# AIO_tracker_V1_0.net
KiCad netlist of a schematic drawn in EAGLE
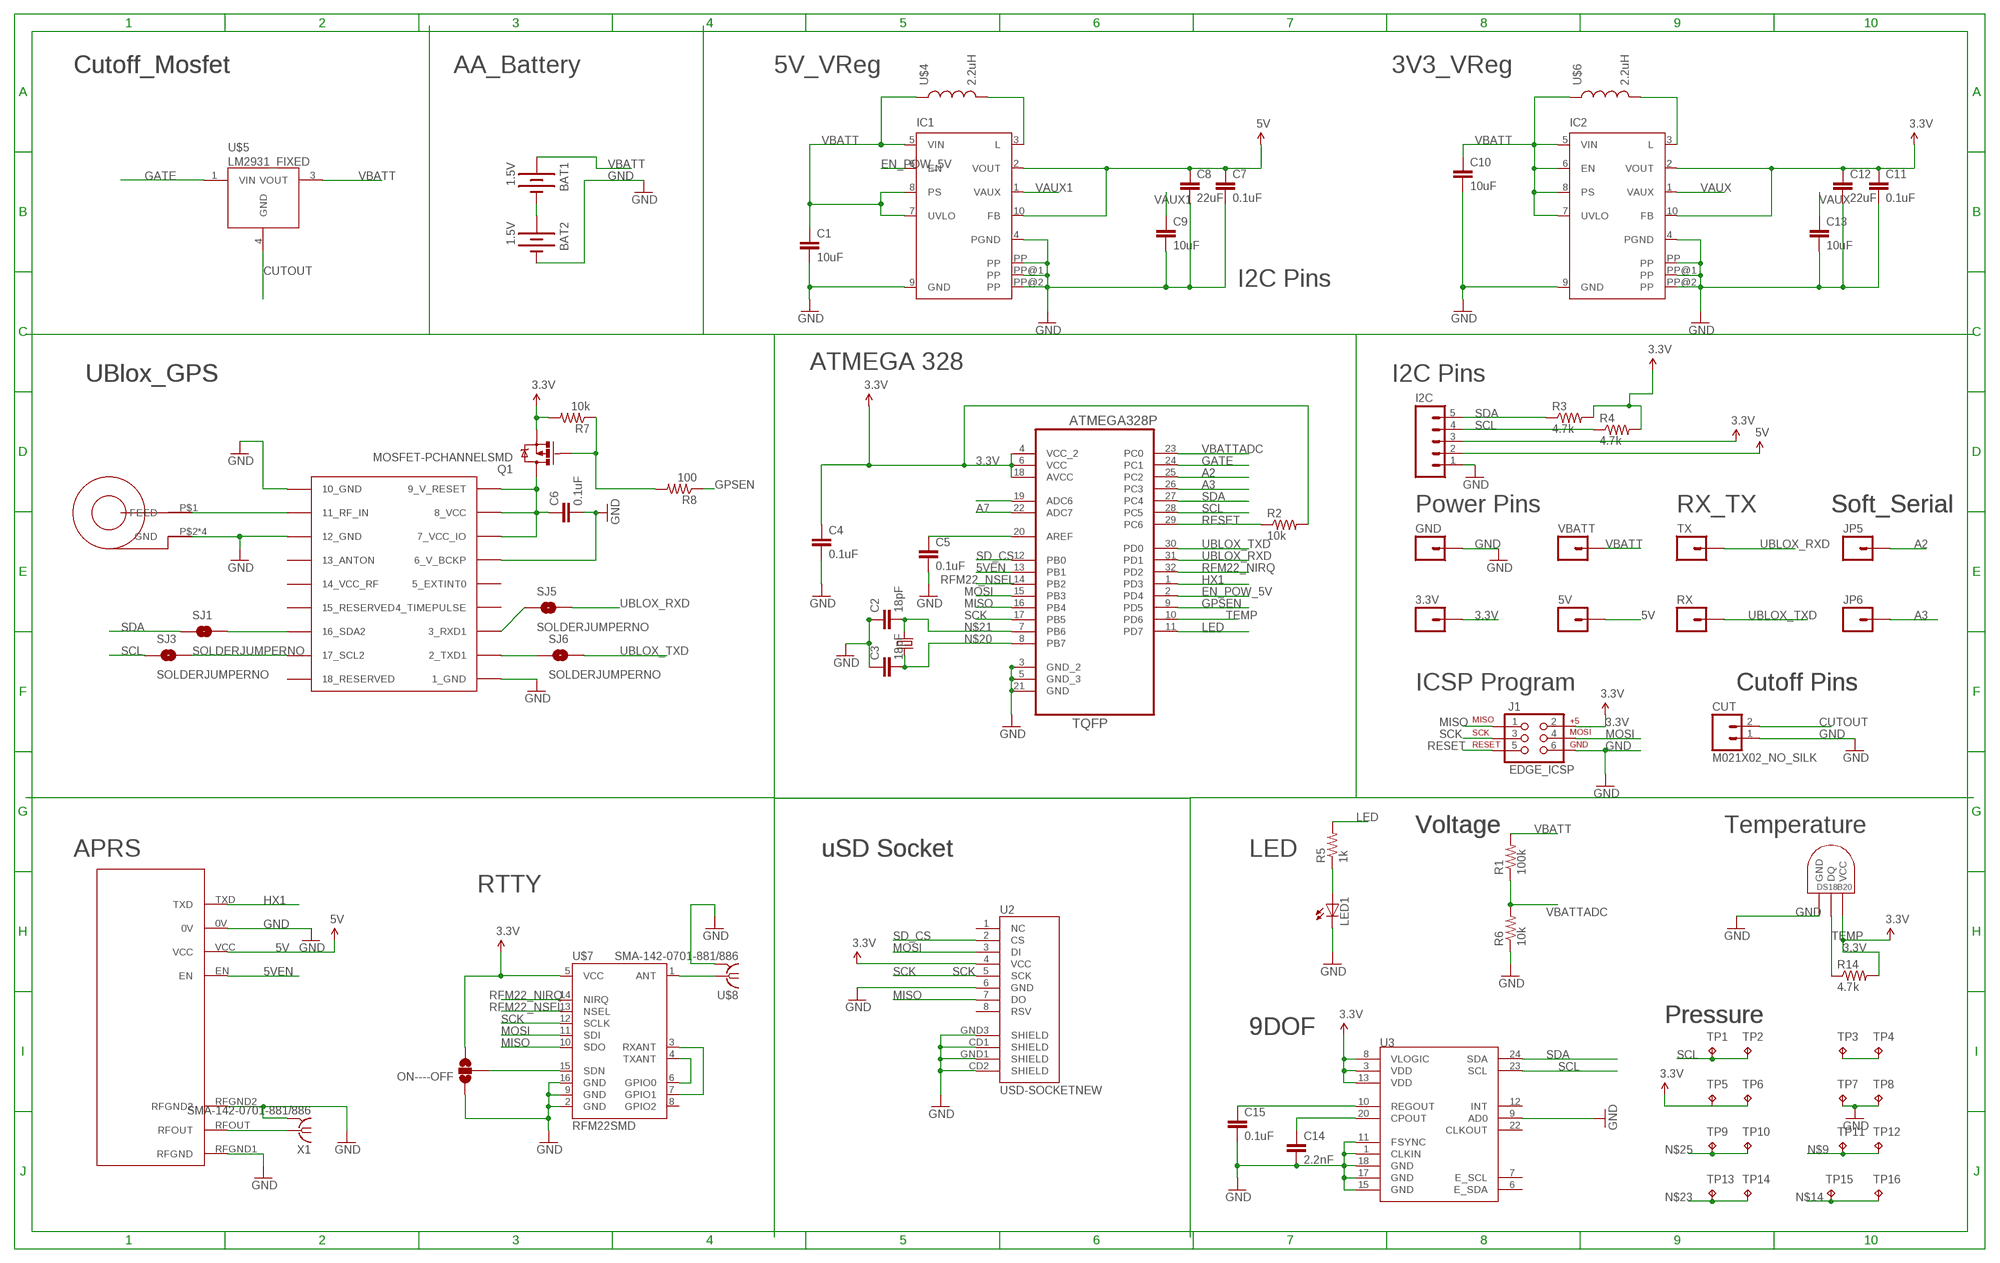
[diagram p0: schematic, sheet 1]

(export (version "E")
  (design (tool "Eeschema 10.0.6"))
  (components
    (comp (ref "3.3V")
      (value "M01SMDNS")
      (footprint "eagle-import:1X01NS")
      (libsource (lib "eagle-import") (part "M01SMDNS"))
    )
    (comp (ref "5V")
      (value "M01SMDNS")
      (footprint "eagle-import:1X01NS")
      (libsource (lib "eagle-import") (part "M01SMDNS"))
    )
    (comp (ref "BAT1")
      (value "1.5V")
      (footprint "eagle-import:BATTERY-AA-KIT")
      (libsource (lib "eagle-import") (part "BATTERYAA-KIT"))
    )
    (comp (ref "BAT2")
      (value "1.5V")
      (footprint "eagle-import:BATTERY-AA-KIT")
      (libsource (lib "eagle-import") (part "BATTERYAA-KIT"))
    )
    (comp (ref "C1")
      (value "10uF")
      (footprint "eagle-import:0805")
      (libsource (lib "eagle-import") (part "CAP0805"))
    )
    (comp (ref "C2")
      (value "18pF")
      (footprint "eagle-import:0603-CAP")
      (libsource (lib "eagle-import") (part "CAP0603-CAP"))
    )
    (comp (ref "C3")
      (value "18pF")
      (footprint "eagle-import:0603-CAP")
      (libsource (lib "eagle-import") (part "CAP0603-CAP"))
    )
    (comp (ref "C4")
      (value "0.1uF")
      (footprint "eagle-import:0603-CAP")
      (libsource (lib "eagle-import") (part "CAP0603-CAP"))
    )
    (comp (ref "C5")
      (value "0.1uF")
      (footprint "eagle-import:0603-CAP")
      (libsource (lib "eagle-import") (part "CAP0603-CAP"))
    )
    (comp (ref "C6")
      (value "0.1uF")
      (footprint "eagle-import:0603-CAP")
      (libsource (lib "eagle-import") (part "CAP0603-CAP"))
    )
    (comp (ref "C7")
      (value "0.1uF")
      (footprint "eagle-import:0603-CAP")
      (libsource (lib "eagle-import") (part "CAP0603-CAP"))
    )
    (comp (ref "C8")
      (value "22uF")
      (footprint "eagle-import:0805")
      (libsource (lib "eagle-import") (part "CAP0805"))
    )
    (comp (ref "C9")
      (value "10uF")
      (footprint "eagle-import:0805")
      (libsource (lib "eagle-import") (part "CAP0805"))
    )
    (comp (ref "C10")
      (value "10uF")
      (footprint "eagle-import:0805")
      (libsource (lib "eagle-import") (part "CAP0805"))
    )
    (comp (ref "C11")
      (value "0.1uF")
      (footprint "eagle-import:0603-CAP")
      (libsource (lib "eagle-import") (part "CAP0603-CAP"))
    )
    (comp (ref "C12")
      (value "22uF")
      (footprint "eagle-import:0805")
      (libsource (lib "eagle-import") (part "CAP0805"))
    )
    (comp (ref "C13")
      (value "10uF")
      (footprint "eagle-import:0805")
      (libsource (lib "eagle-import") (part "CAP0805"))
    )
    (comp (ref "C14")
      (value "2.2nF")
      (footprint "eagle-import:0603-CAP")
      (libsource (lib "eagle-import") (part "CAP0603-CAP"))
    )
    (comp (ref "C15")
      (value "0.1uF")
      (footprint "eagle-import:0603-CAP")
      (libsource (lib "eagle-import") (part "CAP0603-CAP"))
    )
    (comp (ref "CUT")
      (value "M021X02_NO_SILK")
      (footprint "eagle-import:1X02_NO_SILK")
      (libsource (lib "eagle-import") (part "M021X02_NO_SILK"))
    )
    (comp (ref "GND")
      (value "M01SMDNS")
      (footprint "eagle-import:1X01NS")
      (libsource (lib "eagle-import") (part "M01SMDNS"))
    )
    (comp (ref "I2C")
      (value "M05NO_SILK")
      (footprint "eagle-import:1X05_NO_SILK")
      (libsource (lib "eagle-import") (part "M05NO_SILK"))
    )
    (comp (ref "IC1")
      (value "TPS61201")
      (footprint "eagle-import:S-PDSO-N10")
      (fields (field (name "MPN") "TPS61201DRCT"))
      (libsource (lib "eagle-import") (part "TPS61201"))
    )
    (comp (ref "IC2")
      (value "TPS61201")
      (footprint "eagle-import:S-PDSO-N10")
      (fields (field (name "MPN") "TPS61201DRCT"))
      (libsource (lib "eagle-import") (part "TPS61201"))
    )
    (comp (ref "J1")
      (value "EDGE_ICSP")
      (footprint "eagle-import:EDGE_MOUNTED_ICSP")
      (libsource (lib "eagle-import") (part "EDGE_ICSP"))
    )
    (comp (ref "JP5")
      (value "M01PTH")
      (footprint "eagle-import:1X01")
      (libsource (lib "eagle-import") (part "M01PTH"))
    )
    (comp (ref "JP6")
      (value "M01PTH")
      (footprint "eagle-import:1X01")
      (libsource (lib "eagle-import") (part "M01PTH"))
    )
    (comp (ref "LED1")
      (value "LED0603")
      (footprint "eagle-import:LED-0603")
      (libsource (lib "eagle-import") (part "LED0603"))
    )
    (comp (ref "ON----OFF")
      (value "SOLDERJUMPER_2WAY-OLDT")
      (footprint "eagle-import:SJ_2")
      (libsource (lib "eagle-import") (part "SOLDERJUMPER_2WAY-OLDT"))
    )
    (comp (ref "Q1")
      (value "MOSFET-PCHANNELSMD")
      (footprint "eagle-import:SOT23-3")
      (libsource (lib "eagle-import") (part "MOSFET-PCHANNELSMD"))
    )
    (comp (ref "R1")
      (value "100k")
      (footprint "eagle-import:0603-RES")
      (libsource (lib "eagle-import") (part "RESISTOR0603-RES"))
    )
    (comp (ref "R2")
      (value "10k")
      (footprint "eagle-import:0603-RES")
      (libsource (lib "eagle-import") (part "RESISTOR0603-RES"))
    )
    (comp (ref "R3")
      (value "4.7k")
      (footprint "eagle-import:0603-RES")
      (libsource (lib "eagle-import") (part "RESISTOR0603-RES"))
    )
    (comp (ref "R4")
      (value "4.7k")
      (footprint "eagle-import:0603-RES")
      (libsource (lib "eagle-import") (part "RESISTOR0603-RES"))
    )
    (comp (ref "R5")
      (value "1k")
      (footprint "eagle-import:0603-RES")
      (libsource (lib "eagle-import") (part "RESISTOR0603-RES"))
    )
    (comp (ref "R6")
      (value "10k")
      (footprint "eagle-import:0603-RES")
      (libsource (lib "eagle-import") (part "RESISTOR0603-RES"))
    )
    (comp (ref "R7")
      (value "10k")
      (footprint "eagle-import:0603-RES")
      (libsource (lib "eagle-import") (part "RESISTOR0603-RES"))
    )
    (comp (ref "R8")
      (value "100")
      (footprint "eagle-import:0603-RES")
      (libsource (lib "eagle-import") (part "RESISTOR0603-RES"))
    )
    (comp (ref "R14")
      (value "4.7k")
      (footprint "eagle-import:0603-RES")
      (libsource (lib "eagle-import") (part "RESISTOR0603-RES"))
    )
    (comp (ref "RX")
      (value "M01PTH")
      (footprint "eagle-import:1X01")
      (libsource (lib "eagle-import") (part "M01PTH"))
    )
    (comp (ref "SJ1")
      (value "SOLDERJUMPERNO")
      (footprint "eagle-import:SJ_2S-NO")
      (libsource (lib "eagle-import") (part "SOLDERJUMPERNO"))
    )
    (comp (ref "SJ3")
      (value "SOLDERJUMPERNO")
      (footprint "eagle-import:SJ_2S-NO")
      (libsource (lib "eagle-import") (part "SOLDERJUMPERNO"))
    )
    (comp (ref "SJ5")
      (value "SOLDERJUMPERNO")
      (footprint "eagle-import:SJ_2S-NO")
      (libsource (lib "eagle-import") (part "SOLDERJUMPERNO"))
    )
    (comp (ref "SJ6")
      (value "SOLDERJUMPERNO")
      (footprint "eagle-import:SJ_2S-NO")
      (libsource (lib "eagle-import") (part "SOLDERJUMPERNO"))
    )
    (comp (ref "TP1")
      (value "TPTP10SQ")
      (footprint "eagle-import:TP10SQ")
      (libsource (lib "eagle-import") (part "TPTP10SQ"))
    )
    (comp (ref "TP2")
      (value "TPTP10SQ")
      (footprint "eagle-import:TP10SQ")
      (libsource (lib "eagle-import") (part "TPTP10SQ"))
    )
    (comp (ref "TP3")
      (value "TPTP10SQ")
      (footprint "eagle-import:TP10SQ")
      (libsource (lib "eagle-import") (part "TPTP10SQ"))
    )
    (comp (ref "TP4")
      (value "TPTP10SQ")
      (footprint "eagle-import:TP10SQ")
      (libsource (lib "eagle-import") (part "TPTP10SQ"))
    )
    (comp (ref "TP5")
      (value "TPTP10SQ")
      (footprint "eagle-import:TP10SQ")
      (libsource (lib "eagle-import") (part "TPTP10SQ"))
    )
    (comp (ref "TP6")
      (value "TPTP10SQ")
      (footprint "eagle-import:TP10SQ")
      (libsource (lib "eagle-import") (part "TPTP10SQ"))
    )
    (comp (ref "TP7")
      (value "TPTP10SQ")
      (footprint "eagle-import:TP10SQ")
      (libsource (lib "eagle-import") (part "TPTP10SQ"))
    )
    (comp (ref "TP8")
      (value "TPTP10SQ")
      (footprint "eagle-import:TP10SQ")
      (libsource (lib "eagle-import") (part "TPTP10SQ"))
    )
    (comp (ref "TP9")
      (value "TPTP10SQ")
      (footprint "eagle-import:TP10SQ")
      (libsource (lib "eagle-import") (part "TPTP10SQ"))
    )
    (comp (ref "TP10")
      (value "TPTP10SQ")
      (footprint "eagle-import:TP10SQ")
      (libsource (lib "eagle-import") (part "TPTP10SQ"))
    )
    (comp (ref "TP11")
      (value "TPTP10SQ")
      (footprint "eagle-import:TP10SQ")
      (libsource (lib "eagle-import") (part "TPTP10SQ"))
    )
    (comp (ref "TP12")
      (value "TPTP10SQ")
      (footprint "eagle-import:TP10SQ")
      (libsource (lib "eagle-import") (part "TPTP10SQ"))
    )
    (comp (ref "TP13")
      (value "TPTP10SQ")
      (footprint "eagle-import:TP10SQ")
      (libsource (lib "eagle-import") (part "TPTP10SQ"))
    )
    (comp (ref "TP14")
      (value "TPTP10SQ")
      (footprint "eagle-import:TP10SQ")
      (libsource (lib "eagle-import") (part "TPTP10SQ"))
    )
    (comp (ref "TP15")
      (value "TPTP10SQ")
      (footprint "eagle-import:TP10SQ")
      (libsource (lib "eagle-import") (part "TPTP10SQ"))
    )
    (comp (ref "TP16")
      (value "TPTP10SQ")
      (footprint "eagle-import:TP10SQ")
      (libsource (lib "eagle-import") (part "TPTP10SQ"))
    )
    (comp (ref "TX")
      (value "M01PTH")
      (footprint "eagle-import:1X01")
      (libsource (lib "eagle-import") (part "M01PTH"))
    )
    (comp (ref "U$1")
      (value "UBLOX_MAX")
      (footprint "eagle-import:UBLOX_MAX")
      (libsource (lib "eagle-import") (part "UBLOX_MAX"))
    )
    (comp (ref "U$2")
      (value "JDGA-REMQV-ANTENNA")
      (footprint "eagle-import:JDGA-RIGID_COMBO_PAD")
      (libsource (lib "eagle-import") (part "JDGA-REMQV-ANTENNA"))
    )
    (comp (ref "U$3")
      (value "NTX2-VERTICAL")
      (footprint "eagle-import:NTX2-VERTICAL")
      (libsource (lib "eagle-import") (part "NTX2-VERTICAL"))
    )
    (comp (ref "U$4")
      (value "2.2uH")
      (footprint "eagle-import:COILCRAFT_MSS5131")
      (libsource (lib "eagle-import") (part "COILCRAFT-MSS5131"))
    )
    (comp (ref "U$5")
      (value "LM2931_FIXED")
      (footprint "eagle-import:DPAK")
      (libsource (lib "eagle-import") (part "LM2931_FIXED"))
    )
    (comp (ref "U$6")
      (value "2.2uH")
      (footprint "eagle-import:COILCRAFT_MSS5131")
      (libsource (lib "eagle-import") (part "COILCRAFT-MSS5131"))
    )
    (comp (ref "U$7")
      (value "RFM22SMD")
      (footprint "eagle-import:RFM22-XXX-S2")
      (libsource (lib "eagle-import") (part "RFM22SMD"))
    )
    (comp (ref "U$8")
      (value "SMA-142-0701-881/886")
      (footprint "eagle-import:J502-ND-142-0701-881_886")
      (fields (field (name "MF") "JOHNSON COMPONENTS") (field (name "MPN") "142-0701-881"))
      (libsource (lib "eagle-import") (part "SMA-142-0701-881/886"))
    )
    (comp (ref "U$9")
      (value "DS1820")
      (footprint "eagle-import:µSOP8")
      (libsource (lib "eagle-import") (part "DS1820"))
    )
    (comp (ref "U1")
      (value "ATMEGA328P-AU")
      (footprint "eagle-import:QFP80P900X900X120-32N")
      (libsource (lib "eagle-import") (part "ATMEGA328P-AU"))
    )
    (comp (ref "U2")
      (value "USD-SOCKETNEW")
      (footprint "eagle-import:MICRO-SD-SOCKET-PP")
      (libsource (lib "eagle-import") (part "USD-SOCKETNEW"))
    )
    (comp (ref "U3")
      (value "MPU-9150QFN-24-NP")
      (footprint "eagle-import:QFN-24-NP")
      (libsource (lib "eagle-import") (part "MPU-9150QFN-24-NP"))
    )
    (comp (ref "VBATT")
      (value "M01SMDNS")
      (footprint "eagle-import:1X01NS")
      (libsource (lib "eagle-import") (part "M01SMDNS"))
    )
    (comp (ref "X1")
      (value "SMA-142-0701-881/886")
      (footprint "eagle-import:J502-ND-142-0701-881_886")
      (fields (field (name "MF") "JOHNSON COMPONENTS") (field (name "MPN") "142-0701-881"))
      (libsource (lib "eagle-import") (part "SMA-142-0701-881/886"))
    )
    (comp (ref "Y1")
      (value "ABRACON_ABM3_CRYSTAL")
      (footprint "eagle-import:ABRACON_ABM3_CRYSTAL")
      (libsource (lib "eagle-import") (part "ABRACON_ABM3_CRYSTAL"))
    )
  )
  (nets
    (net (code "1") (name "/5VEN") (class "Default")
      (node (ref "U$3") (pin "EN") (pinfunction "EN_EN") (pintype "bidirectional"))
      (node (ref "U1") (pin "13") (pinfunction "PB1_13") (pintype "bidirectional"))
    )
    (net (code "2") (name "/A2") (class "Default")
      (node (ref "JP5") (pin "1") (pinfunction "1_1") (pintype "passive"))
      (node (ref "U1") (pin "25") (pinfunction "PC2_25") (pintype "bidirectional"))
    )
    (net (code "3") (name "/A3") (class "Default")
      (node (ref "JP6") (pin "1") (pinfunction "1_1") (pintype "passive"))
      (node (ref "U1") (pin "26") (pinfunction "PC3_26") (pintype "bidirectional"))
    )
    (net (code "4") (name "/A7") (class "Default")
      (node (ref "U1") (pin "22") (pinfunction "ADC7_22") (pintype "input"))
    )
    (net (code "5") (name "/CUTOUT") (class "Default")
      (node (ref "CUT") (pin "2") (pinfunction "2_2") (pintype "passive"))
      (node (ref "U$5") (pin "4") (pinfunction "GND_4") (pintype "bidirectional"))
    )
    (net (code "6") (name "/EN_POW_5V") (class "Default")
      (node (ref "IC1") (pin "6") (pinfunction "EN_6") (pintype "input"))
      (node (ref "U1") (pin "2") (pinfunction "PD4_2") (pintype "bidirectional"))
    )
    (net (code "7") (name "/GATE") (class "Default")
      (node (ref "U$5") (pin "1") (pinfunction "VIN_1") (pintype "bidirectional"))
      (node (ref "U1") (pin "24") (pinfunction "PC1_24") (pintype "bidirectional"))
    )
    (net (code "8") (name "/GPSEN") (class "Default")
      (node (ref "R8") (pin "1") (pinfunction "1_1") (pintype "passive"))
      (node (ref "U1") (pin "9") (pinfunction "PD5_9") (pintype "bidirectional"))
    )
    (net (code "9") (name "/HX1") (class "Default")
      (node (ref "U$3") (pin "TXD") (pinfunction "TXD_TXD") (pintype "bidirectional"))
      (node (ref "U1") (pin "1") (pinfunction "PD3_1") (pintype "bidirectional"))
    )
    (net (code "10") (name "/LED") (class "Default")
      (node (ref "R5") (pin "2") (pinfunction "2_2") (pintype "passive"))
      (node (ref "U1") (pin "11") (pinfunction "PD7_11") (pintype "bidirectional"))
    )
    (net (code "11") (name "/MISO") (class "Default")
      (node (ref "J1") (pin "1") (pinfunction "1_1") (pintype "passive"))
      (node (ref "U$7") (pin "10") (pinfunction "SDO_10") (pintype "output"))
      (node (ref "U1") (pin "16") (pinfunction "PB4_16") (pintype "bidirectional"))
      (node (ref "U2") (pin "7") (pinfunction "DO_7") (pintype "bidirectional"))
    )
    (net (code "12") (name "/MOSI") (class "Default")
      (node (ref "J1") (pin "4") (pinfunction "4_4") (pintype "passive"))
      (node (ref "U$7") (pin "11") (pinfunction "SDI_11") (pintype "input"))
      (node (ref "U1") (pin "15") (pinfunction "PB3_15") (pintype "bidirectional"))
      (node (ref "U2") (pin "3") (pinfunction "DI_3") (pintype "bidirectional"))
    )
    (net (code "13") (name "/N$9") (class "Default")
      (node (ref "TP11") (pin "TP") (pinfunction "TP_TP") (pintype "input"))
      (node (ref "TP12") (pin "TP") (pinfunction "TP_TP") (pintype "input"))
    )
    (net (code "14") (name "/N$14") (class "Default")
      (node (ref "TP15") (pin "TP") (pinfunction "TP_TP") (pintype "input"))
      (node (ref "TP16") (pin "TP") (pinfunction "TP_TP") (pintype "input"))
    )
    (net (code "15") (name "/N$20") (class "Default")
      (node (ref "C3") (pin "2") (pinfunction "2_2") (pintype "passive"))
      (node (ref "U1") (pin "8") (pinfunction "PB7_8") (pintype "bidirectional"))
      (node (ref "Y1") (pin "P$1") (pinfunction "1_P$1") (pintype "passive"))
    )
    (net (code "16") (name "/N$21") (class "Default")
      (node (ref "C2") (pin "2") (pinfunction "2_2") (pintype "passive"))
      (node (ref "U1") (pin "7") (pinfunction "PB6_7") (pintype "bidirectional"))
      (node (ref "Y1") (pin "P$2") (pinfunction "2_P$2") (pintype "passive"))
    )
    (net (code "17") (name "/N$23") (class "Default")
      (node (ref "TP13") (pin "TP") (pinfunction "TP_TP") (pintype "input"))
      (node (ref "TP14") (pin "TP") (pinfunction "TP_TP") (pintype "input"))
    )
    (net (code "18") (name "/N$25") (class "Default")
      (node (ref "TP10") (pin "TP") (pinfunction "TP_TP") (pintype "input"))
      (node (ref "TP9") (pin "TP") (pinfunction "TP_TP") (pintype "input"))
    )
    (net (code "19") (name "/RESET") (class "Default")
      (node (ref "J1") (pin "5") (pinfunction "5_5") (pintype "passive"))
      (node (ref "R2") (pin "1") (pinfunction "1_1") (pintype "passive"))
      (node (ref "U1") (pin "29") (pinfunction "PC6_29") (pintype "bidirectional"))
    )
    (net (code "20") (name "/RFM22_NIRQ") (class "Default")
      (node (ref "U$7") (pin "14") (pinfunction "NIRQ_14") (pintype "output"))
      (node (ref "U1") (pin "32") (pinfunction "PD2_32") (pintype "bidirectional"))
    )
    (net (code "21") (name "/RFM22_NSEL") (class "Default")
      (node (ref "U$7") (pin "13") (pinfunction "NSEL_13") (pintype "input"))
      (node (ref "U1") (pin "14") (pinfunction "PB2_14") (pintype "bidirectional"))
    )
    (net (code "22") (name "/SCK") (class "Default")
      (node (ref "J1") (pin "3") (pinfunction "3_3") (pintype "passive"))
      (node (ref "U$7") (pin "12") (pinfunction "SCLK_12") (pintype "input"))
      (node (ref "U1") (pin "17") (pinfunction "PB5_17") (pintype "bidirectional"))
      (node (ref "U2") (pin "5") (pinfunction "SCK_5") (pintype "bidirectional"))
    )
    (net (code "23") (name "/SCL") (class "Default")
      (node (ref "I2C") (pin "4") (pinfunction "4_4") (pintype "passive"))
      (node (ref "R4") (pin "1") (pinfunction "1_1") (pintype "passive"))
      (node (ref "SJ3") (pin "1") (pinfunction "1_1") (pintype "passive"))
      (node (ref "TP1") (pin "TP") (pinfunction "TP_TP") (pintype "input"))
      (node (ref "TP2") (pin "TP") (pinfunction "TP_TP") (pintype "input"))
      (node (ref "U1") (pin "28") (pinfunction "PC5_28") (pintype "bidirectional"))
      (node (ref "U3") (pin "23") (pinfunction "SCL_23") (pintype "bidirectional"))
    )
    (net (code "24") (name "/SDA") (class "Default")
      (node (ref "I2C") (pin "5") (pinfunction "5_5") (pintype "passive"))
      (node (ref "R3") (pin "1") (pinfunction "1_1") (pintype "passive"))
      (node (ref "SJ1") (pin "1") (pinfunction "1_1") (pintype "passive"))
      (node (ref "TP3") (pin "TP") (pinfunction "TP_TP") (pintype "input"))
      (node (ref "TP4") (pin "TP") (pinfunction "TP_TP") (pintype "input"))
      (node (ref "U1") (pin "27") (pinfunction "PC4_27") (pintype "bidirectional"))
      (node (ref "U3") (pin "24") (pinfunction "SDA_24") (pintype "bidirectional"))
    )
    (net (code "25") (name "/SD_CS") (class "Default")
      (node (ref "U1") (pin "12") (pinfunction "PB0_12") (pintype "bidirectional"))
      (node (ref "U2") (pin "2") (pinfunction "CS_2") (pintype "bidirectional"))
    )
    (net (code "26") (name "/TEMP") (class "Default")
      (node (ref "R14") (pin "1") (pinfunction "1_1") (pintype "passive"))
      (node (ref "U$9") (pin "1") (pinfunction "DQ_1") (pintype "bidirectional"))
      (node (ref "U1") (pin "10") (pinfunction "PD6_10") (pintype "bidirectional"))
    )
    (net (code "27") (name "/UBLOX_RXD") (class "Default")
      (node (ref "SJ5") (pin "2") (pinfunction "2_2") (pintype "passive"))
      (node (ref "TX") (pin "1") (pinfunction "1_1") (pintype "passive"))
      (node (ref "U1") (pin "31") (pinfunction "PD1_31") (pintype "bidirectional"))
    )
    (net (code "28") (name "/UBLOX_TXD") (class "Default")
      (node (ref "RX") (pin "1") (pinfunction "1_1") (pintype "passive"))
      (node (ref "SJ6") (pin "2") (pinfunction "2_2") (pintype "passive"))
      (node (ref "U1") (pin "30") (pinfunction "PD0_30") (pintype "bidirectional"))
    )
    (net (code "29") (name "/VAUX") (class "Default")
      (node (ref "C13") (pin "1") (pinfunction "1_1") (pintype "passive"))
      (node (ref "IC2") (pin "1") (pinfunction "VAUX_1") (pintype "bidirectional"))
    )
    (net (code "30") (name "/VAUX1") (class "Default")
      (node (ref "C9") (pin "1") (pinfunction "1_1") (pintype "passive"))
      (node (ref "IC1") (pin "1") (pinfunction "VAUX_1") (pintype "bidirectional"))
    )
    (net (code "31") (name "/VBATT") (class "Default")
      (node (ref "BAT1") (pin "PWR@1") (pinfunction "+_PWR@1") (pintype "power_in"))
      (node (ref "C1") (pin "1") (pinfunction "1_1") (pintype "passive"))
      (node (ref "C10") (pin "1") (pinfunction "1_1") (pintype "passive"))
      (node (ref "IC1") (pin "5") (pinfunction "VIN_5") (pintype "input"))
      (node (ref "IC1") (pin "7") (pinfunction "UVLO_7") (pintype "input"))
      (node (ref "IC1") (pin "8") (pinfunction "PS_8") (pintype "input"))
      (node (ref "IC2") (pin "5") (pinfunction "VIN_5") (pintype "input"))
      (node (ref "IC2") (pin "6") (pinfunction "EN_6") (pintype "input"))
      (node (ref "IC2") (pin "7") (pinfunction "UVLO_7") (pintype "input"))
      (node (ref "IC2") (pin "8") (pinfunction "PS_8") (pintype "input"))
      (node (ref "R1") (pin "2") (pinfunction "2_2") (pintype "passive"))
      (node (ref "U$4") (pin "P$2") (pinfunction "1_P$2") (pintype "passive"))
      (node (ref "U$5") (pin "3") (pinfunction "VOUT_3") (pintype "bidirectional"))
      (node (ref "U$6") (pin "P$2") (pinfunction "1_P$2") (pintype "passive"))
      (node (ref "VBATT") (pin "1") (pinfunction "1_1") (pintype "passive"))
    )
    (net (code "32") (name "/VBATTADC") (class "Default")
      (node (ref "R1") (pin "1") (pinfunction "1_1") (pintype "passive"))
      (node (ref "R6") (pin "2") (pinfunction "2_2") (pintype "passive"))
      (node (ref "U1") (pin "23") (pinfunction "PC0_23") (pintype "bidirectional"))
    )
    (net (code "33") (name "3.3V") (class "Default")
      (node (ref "3.3V") (pin "1") (pinfunction "1_1") (pintype "passive"))
      (node (ref "C11") (pin "1") (pinfunction "1_1") (pintype "passive"))
      (node (ref "C12") (pin "1") (pinfunction "1_1") (pintype "passive"))
      (node (ref "C4") (pin "1") (pinfunction "1_1") (pintype "passive"))
      (node (ref "I2C") (pin "3") (pinfunction "3_3") (pintype "passive"))
      (node (ref "IC2") (pin "10") (pinfunction "FB_10") (pintype "input"))
      (node (ref "IC2") (pin "2") (pinfunction "VOUT_2") (pintype "passive"))
      (node (ref "J1") (pin "2") (pinfunction "2_2") (pintype "passive"))
      (node (ref "ON----OFF") (pin "3") (pinfunction "3_3") (pintype "passive"))
      (node (ref "Q1") (pin "2") (pinfunction "S_2") (pintype "passive"))
      (node (ref "R14") (pin "2") (pinfunction "2_2") (pintype "passive"))
      (node (ref "R2") (pin "2") (pinfunction "2_2") (pintype "passive"))
      (node (ref "R3") (pin "2") (pinfunction "2_2") (pintype "passive"))
      (node (ref "R4") (pin "2") (pinfunction "2_2") (pintype "passive"))
      (node (ref "R7") (pin "2") (pinfunction "2_2") (pintype "passive"))
      (node (ref "TP5") (pin "TP") (pinfunction "TP_TP") (pintype "input"))
      (node (ref "TP6") (pin "TP") (pinfunction "TP_TP") (pintype "input"))
      (node (ref "U$7") (pin "5") (pinfunction "VCC_5") (pintype "bidirectional"))
      (node (ref "U$9") (pin "8") (pinfunction "VCC_8") (pintype "power_in"))
      (node (ref "U1") (pin "18") (pinfunction "AVCC_18") (pintype "power_in"))
      (node (ref "U1") (pin "4") (pinfunction "VCC_2_4") (pintype "power_in"))
      (node (ref "U1") (pin "6") (pinfunction "VCC_6") (pintype "power_in"))
      (node (ref "U2") (pin "4") (pinfunction "VCC_4") (pintype "bidirectional"))
      (node (ref "U3") (pin "13") (pinfunction "VDD_13") (pintype "bidirectional"))
      (node (ref "U3") (pin "3") (pinfunction "VDD_3") (pintype "bidirectional"))
      (node (ref "U3") (pin "8") (pinfunction "VLOGIC_8") (pintype "bidirectional"))
    )
    (net (code "34") (name "5V") (class "Default")
      (node (ref "5V") (pin "1") (pinfunction "1_1") (pintype "passive"))
      (node (ref "C7") (pin "1") (pinfunction "1_1") (pintype "passive"))
      (node (ref "C8") (pin "1") (pinfunction "1_1") (pintype "passive"))
      (node (ref "I2C") (pin "2") (pinfunction "2_2") (pintype "passive"))
      (node (ref "IC1") (pin "10") (pinfunction "FB_10") (pintype "input"))
      (node (ref "IC1") (pin "2") (pinfunction "VOUT_2") (pintype "passive"))
      (node (ref "U$3") (pin "VCC") (pinfunction "VCC_VCC") (pintype "bidirectional"))
    )
    (net (code "35") (name "GND") (class "Default")
      (node (ref "BAT2") (pin "GND@1") (pinfunction "-_GND@1") (pintype "power_in"))
      (node (ref "C1") (pin "2") (pinfunction "2_2") (pintype "passive"))
      (node (ref "C10") (pin "2") (pinfunction "2_2") (pintype "passive"))
      (node (ref "C11") (pin "2") (pinfunction "2_2") (pintype "passive"))
      (node (ref "C12") (pin "2") (pinfunction "2_2") (pintype "passive"))
      (node (ref "C13") (pin "2") (pinfunction "2_2") (pintype "passive"))
      (node (ref "C14") (pin "2") (pinfunction "2_2") (pintype "passive"))
      (node (ref "C15") (pin "2") (pinfunction "2_2") (pintype "passive"))
      (node (ref "C2") (pin "1") (pinfunction "1_1") (pintype "passive"))
      (node (ref "C3") (pin "1") (pinfunction "1_1") (pintype "passive"))
      (node (ref "C4") (pin "2") (pinfunction "2_2") (pintype "passive"))
      (node (ref "C5") (pin "2") (pinfunction "2_2") (pintype "passive"))
      (node (ref "C6") (pin "2") (pinfunction "2_2") (pintype "passive"))
      (node (ref "C7") (pin "2") (pinfunction "2_2") (pintype "passive"))
      (node (ref "C8") (pin "2") (pinfunction "2_2") (pintype "passive"))
      (node (ref "C9") (pin "2") (pinfunction "2_2") (pintype "passive"))
      (node (ref "CUT") (pin "1") (pinfunction "1_1") (pintype "passive"))
      (node (ref "GND") (pin "1") (pinfunction "1_1") (pintype "passive"))
      (node (ref "I2C") (pin "1") (pinfunction "1_1") (pintype "passive"))
      (node (ref "IC1") (pin "4") (pinfunction "PGND_4") (pintype "power_in"))
      (node (ref "IC1") (pin "9") (pinfunction "GND_9") (pintype "power_in"))
      (node (ref "IC1") (pin "PP") (pinfunction "PP_PP") (pintype "power_in"))
      (node (ref "IC1") (pin "PP@1") (pinfunction "PP_PP@1") (pintype "power_in"))
      (node (ref "IC1") (pin "PP@2") (pinfunction "PP_PP@2") (pintype "power_in"))
      (node (ref "IC2") (pin "4") (pinfunction "PGND_4") (pintype "power_in"))
      (node (ref "IC2") (pin "9") (pinfunction "GND_9") (pintype "power_in"))
      (node (ref "IC2") (pin "PP") (pinfunction "PP_PP") (pintype "power_in"))
      (node (ref "IC2") (pin "PP@1") (pinfunction "PP_PP@1") (pintype "power_in"))
      (node (ref "IC2") (pin "PP@2") (pinfunction "PP_PP@2") (pintype "power_in"))
      (node (ref "J1") (pin "6") (pinfunction "6_6") (pintype "passive"))
      (node (ref "LED1") (pin "C") (pinfunction "C_C") (pintype "passive"))
      (node (ref "ON----OFF") (pin "1") (pinfunction "1_1") (pintype "passive"))
      (node (ref "R6") (pin "1") (pinfunction "1_1") (pintype "passive"))
      (node (ref "TP7") (pin "TP") (pinfunction "TP_TP") (pintype "input"))
      (node (ref "TP8") (pin "TP") (pinfunction "TP_TP") (pintype "input"))
      (node (ref "U$1") (pin "10_GND") (pinfunction "10_GND_10_GND") (pintype "power_in"))
      (node (ref "U$1") (pin "12_GND") (pinfunction "12_GND_12_GND") (pintype "power_in"))
      (node (ref "U$1") (pin "1_GND") (pinfunction "1_GND_1_GND") (pintype "power_in"))
      (node (ref "U$1") (pin "6_V_BCKP") (pinfunction "6_V_BCKP_6_V_BCKP") (pintype "bidirectional"))
      (node (ref "U$2") (pin "P$2") (pinfunction "GND_P$2") (pintype "bidirectional"))
      (node (ref "U$2") (pin "P$3") (pinfunction "GND_P$3") (pintype "bidirectional"))
      (node (ref "U$2") (pin "P$4") (pinfunction "GND_P$4") (pintype "bidirectional"))
      (node (ref "U$2") (pin "P$5") (pinfunction "GND_P$5") (pintype "bidirectional"))
      (node (ref "U$3") (pin "0V") (pinfunction "0V_0V") (pintype "bidirectional"))
      (node (ref "U$3") (pin "RFGND1") (pinfunction "RFGND_RFGND1") (pintype "bidirectional"))
      (node (ref "U$3") (pin "RFGND2") (pinfunction "RFGND2_RFGND2") (pintype "bidirectional"))
      (node (ref "U$7") (pin "16") (pinfunction "GND_16") (pintype "power_in"))
      (node (ref "U$7") (pin "2") (pinfunction "GND_2") (pintype "power_in"))
      (node (ref "U$7") (pin "9") (pinfunction "GND_9") (pintype "power_in"))
      (node (ref "U$8") (pin "G@1") (pinfunction "2_G@1") (pintype "passive"))
      (node (ref "U$8") (pin "G@2") (pinfunction "2_G@2") (pintype "passive"))
      (node (ref "U$8") (pin "G@3") (pinfunction "2_G@3") (pintype "passive"))
      (node (ref "U$8") (pin "G@4") (pinfunction "2_G@4") (pintype "passive"))
      (node (ref "U$9") (pin "4") (pinfunction "GND_4") (pintype "power_in"))
      (node (ref "U1") (pin "21") (pinfunction "GND_21") (pintype "passive"))
      (node (ref "U1") (pin "3") (pinfunction "GND_2_3") (pintype "passive"))
      (node (ref "U1") (pin "5") (pinfunction "GND_3_5") (pintype "passive"))
      (node (ref "U2") (pin "6") (pinfunction "GND_6") (pintype "bidirectional"))
      (node (ref "U2") (pin "CD1") (pinfunction "SHIELD_CD1") (pintype "bidirectional"))
      (node (ref "U2") (pin "CD2") (pinfunction "SHIELD_CD2") (pintype "bidirectional"))
      (node (ref "U2") (pin "GND1") (pinfunction "SHIELD_GND1") (pintype "bidirectional"))
      (node (ref "U2") (pin "GND3") (pinfunction "SHIELD_GND3") (pintype "bidirectional"))
      (node (ref "U3") (pin "1") (pinfunction "CLKIN_1") (pintype "bidirectional"))
      (node (ref "U3") (pin "11") (pinfunction "FSYNC_11") (pintype "bidirectional"))
      (node (ref "U3") (pin "15") (pinfunction "GND_15") (pintype "bidirectional"))
      (node (ref "U3") (pin "17") (pinfunction "GND_17") (pintype "bidirectional"))
      (node (ref "U3") (pin "18") (pinfunction "GND_18") (pintype "bidirectional"))
      (node (ref "U3") (pin "9") (pinfunction "AD0_9") (pintype "bidirectional"))
      (node (ref "X1") (pin "G@1") (pinfunction "2_G@1") (pintype "passive"))
      (node (ref "X1") (pin "G@2") (pinfunction "2_G@2") (pintype "passive"))
      (node (ref "X1") (pin "G@3") (pinfunction "2_G@3") (pintype "passive"))
      (node (ref "X1") (pin "G@4") (pinfunction "2_G@4") (pintype "passive"))
    )
    (net (code "36") (name "Net-(BAT1--)") (class "Default")
      (node (ref "BAT1") (pin "GND@1") (pinfunction "-_GND@1") (pintype "power_in"))
      (node (ref "BAT2") (pin "PWR@1") (pinfunction "+_PWR@1") (pintype "power_in"))
    )
    (net (code "37") (name "Net-(IC1-L)") (class "Default")
      (node (ref "IC1") (pin "3") (pinfunction "L_3") (pintype "input"))
      (node (ref "U$4") (pin "P$1") (pinfunction "2_P$1") (pintype "passive"))
    )
    (net (code "38") (name "Net-(IC2-L)") (class "Default")
      (node (ref "IC2") (pin "3") (pinfunction "L_3") (pintype "input"))
      (node (ref "U$6") (pin "P$1") (pinfunction "2_P$1") (pintype "passive"))
    )
    (net (code "39") (name "Net-(LED1-PadA)") (class "Default")
      (node (ref "LED1") (pin "A") (pinfunction "A_A") (pintype "passive"))
      (node (ref "R5") (pin "1") (pinfunction "1_1") (pintype "passive"))
    )
    (net (code "40") (name "Net-(Q1-D)") (class "Default")
      (node (ref "C6") (pin "1") (pinfunction "1_1") (pintype "passive"))
      (node (ref "Q1") (pin "3") (pinfunction "D_3") (pintype "passive"))
      (node (ref "U$1") (pin "7_VCC_IO") (pinfunction "7_VCC_IO_7_VCC_IO") (pintype "power_in"))
      (node (ref "U$1") (pin "8_VCC") (pinfunction "8_VCC_8_VCC") (pintype "power_in"))
      (node (ref "U$1") (pin "9_V_RESET") (pinfunction "9_V_RESET_9_V_RESET") (pintype "power_in"))
    )
    (net (code "41") (name "Net-(Q1-G)") (class "Default")
      (node (ref "Q1") (pin "1") (pinfunction "G_1") (pintype "passive"))
      (node (ref "R7") (pin "1") (pinfunction "1_1") (pintype "passive"))
      (node (ref "R8") (pin "2") (pinfunction "2_2") (pintype "passive"))
    )
    (net (code "42") (name "Net-(SJ1-Pad2)") (class "Default")
      (node (ref "SJ1") (pin "2") (pinfunction "2_2") (pintype "passive"))
      (node (ref "U$1") (pin "16_SDA2") (pinfunction "16_SDA2_16_SDA2") (pintype "bidirectional"))
    )
    (net (code "43") (name "Net-(SJ3-Pad2)") (class "Default")
      (node (ref "SJ3") (pin "2") (pinfunction "2_2") (pintype "passive"))
      (node (ref "U$1") (pin "17_SCL2") (pinfunction "17_SCL2_17_SCL2") (pintype "bidirectional"))
    )
    (net (code "44") (name "Net-(SJ5-Pad1)") (class "Default")
      (node (ref "SJ5") (pin "1") (pinfunction "1_1") (pintype "passive"))
      (node (ref "U$1") (pin "3_RXD1") (pinfunction "3_RXD1_3_RXD1") (pintype "bidirectional"))
    )
    (net (code "45") (name "Net-(SJ6-Pad1)") (class "Default")
      (node (ref "SJ6") (pin "1") (pinfunction "1_1") (pintype "passive"))
      (node (ref "U$1") (pin "2_TXD1") (pinfunction "2_TXD1_2_TXD1") (pintype "bidirectional"))
    )
    (net (code "46") (name "Net-(U$2-FEED)") (class "Default")
      (node (ref "U$1") (pin "11_RF_IN") (pinfunction "11_RF_IN_11_RF_IN") (pintype "bidirectional"))
      (node (ref "U$2") (pin "P$1") (pinfunction "FEED_P$1") (pintype "bidirectional"))
    )
    (net (code "47") (name "Net-(U$3-PadRFOUT)") (class "Default")
      (node (ref "U$3") (pin "RFOUT") (pinfunction "RFOUT_RFOUT") (pintype "bidirectional"))
      (node (ref "X1") (pin "1") (pinfunction "1_1") (pintype "passive"))
    )
    (net (code "48") (name "Net-(U$7-ANT)") (class "Default")
      (node (ref "U$7") (pin "1") (pinfunction "ANT_1") (pintype "bidirectional"))
      (node (ref "U$8") (pin "1") (pinfunction "1_1") (pintype "passive"))
    )
    (net (code "49") (name "Net-(U$7-GPIO0)") (class "Default")
      (node (ref "U$7") (pin "4") (pinfunction "TXANT_4") (pintype "input"))
      (node (ref "U$7") (pin "6") (pinfunction "GPIO0_6") (pintype "bidirectional"))
    )
    (net (code "50") (name "Net-(U$7-GPIO1)") (class "Default")
      (node (ref "U$7") (pin "3") (pinfunction "RXANT_3") (pintype "input"))
      (node (ref "U$7") (pin "7") (pinfunction "GPIO1_7") (pintype "bidirectional"))
    )
    (net (code "51") (name "Net-(U$7-SDN)") (class "Default")
      (node (ref "ON----OFF") (pin "2") (pinfunction "2_2") (pintype "passive"))
      (node (ref "U$7") (pin "15") (pinfunction "SDN_15") (pintype "bidirectional"))
    )
    (net (code "52") (name "Net-(U1-AREF)") (class "Default")
      (node (ref "C5") (pin "1") (pinfunction "1_1") (pintype "passive"))
      (node (ref "U1") (pin "20") (pinfunction "AREF_20") (pintype "input"))
    )
    (net (code "53") (name "Net-(U3-CPOUT)") (class "Default")
      (node (ref "C14") (pin "1") (pinfunction "1_1") (pintype "passive"))
      (node (ref "U3") (pin "20") (pinfunction "CPOUT_20") (pintype "bidirectional"))
    )
    (net (code "54") (name "Net-(U3-REGOUT)") (class "Default")
      (node (ref "C15") (pin "1") (pinfunction "1_1") (pintype "passive"))
      (node (ref "U3") (pin "10") (pinfunction "REGOUT_10") (pintype "bidirectional"))
    )
    (net (code "55") (name "unconnected-(U$1-Pad4_TIMEPULSE)") (class "Default")
      (node (ref "U$1") (pin "4_TIMEPULSE") (pinfunction "4_TIMEPULSE_4_TIMEPULSE") (pintype "bidirectional"))
    )
    (net (code "56") (name "unconnected-(U$1-Pad5_EXTINT0)") (class "Default")
      (node (ref "U$1") (pin "5_EXTINT0") (pinfunction "5_EXTINT0_5_EXTINT0") (pintype "bidirectional"))
    )
    (net (code "57") (name "unconnected-(U$1-Pad13_ANTON)") (class "Default")
      (node (ref "U$1") (pin "13_ANTON") (pinfunction "13_ANTON_13_ANTON") (pintype "bidirectional"))
    )
    (net (code "58") (name "unconnected-(U$1-Pad14_VCC_RF)") (class "Default")
      (node (ref "U$1") (pin "14_VCC_RF") (pinfunction "14_VCC_RF_14_VCC_RF") (pintype "bidirectional"))
    )
    (net (code "59") (name "unconnected-(U$1-Pad15_RESERVED)") (class "Default")
      (node (ref "U$1") (pin "15_RESERVED") (pinfunction "15_RESERVED_15_RESERVED") (pintype "bidirectional"))
    )
    (net (code "60") (name "unconnected-(U$1-Pad18_RESERVED)") (class "Default")
      (node (ref "U$1") (pin "18_RESERVED") (pinfunction "18_RESERVED_18_RESERVED") (pintype "bidirectional"))
    )
    (net (code "61") (name "unconnected-(U$7-GPIO2-Pad8)") (class "Default")
      (node (ref "U$7") (pin "8") (pinfunction "GPIO2_8") (pintype "bidirectional"))
    )
    (net (code "62") (name "unconnected-(U1-ADC6-Pad19)") (class "Default")
      (node (ref "U1") (pin "19") (pinfunction "ADC6_19") (pintype "bidirectional"))
    )
    (net (code "63") (name "unconnected-(U2-NC-Pad1)") (class "Default")
      (node (ref "U2") (pin "1") (pinfunction "NC_1") (pintype "bidirectional"))
    )
    (net (code "64") (name "unconnected-(U2-RSV-Pad8)") (class "Default")
      (node (ref "U2") (pin "8") (pinfunction "RSV_8") (pintype "bidirectional"))
    )
    (net (code "65") (name "unconnected-(U3-CLKOUT-Pad22)") (class "Default")
      (node (ref "U3") (pin "22") (pinfunction "CLKOUT_22") (pintype "bidirectional"))
    )
    (net (code "66") (name "unconnected-(U3-E_SCL-Pad7)") (class "Default")
      (node (ref "U3") (pin "7") (pinfunction "E_SCL_7") (pintype "bidirectional"))
    )
    (net (code "67") (name "unconnected-(U3-E_SDA-Pad6)") (class "Default")
      (node (ref "U3") (pin "6") (pinfunction "E_SDA_6") (pintype "bidirectional"))
    )
    (net (code "68") (name "unconnected-(U3-INT-Pad12)") (class "Default")
      (node (ref "U3") (pin "12") (pinfunction "INT_12") (pintype "bidirectional"))
    )
  )
)
